# SCHE_TA_THI_THU_PHUONG.net
KiCad netlist of a schematic drawn in Altium Designer
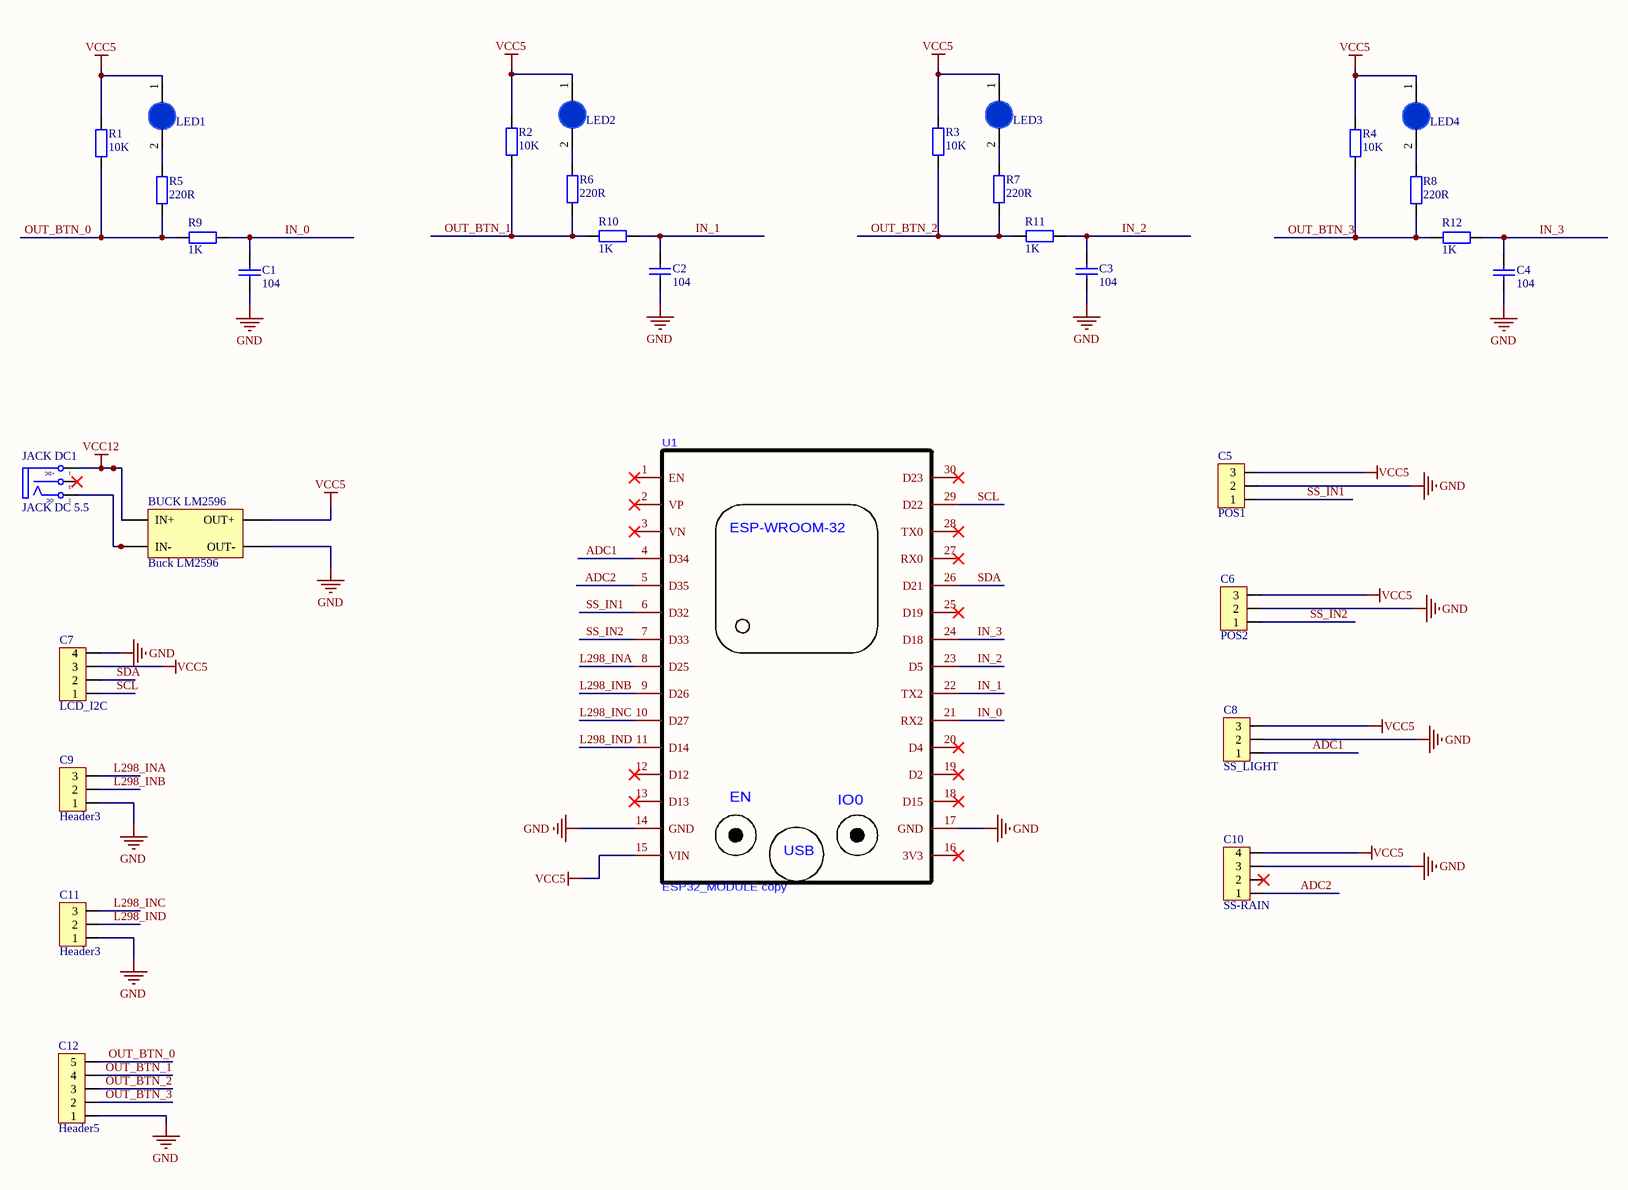
[diagram p0: SCHE_TA_THI_THU_PHUONG.SchDoc]

(export (version "E")
  (design (tool "Eeschema 10.0.6"))
  (components
    (comp (ref "BUCK LM2596")
      (value "Buck LM2596")
      (footprint "BUCK LM2596")
      (libsource (lib "myLib_v1 (1)") (part "Buck LM2596"))
    )
    (comp (ref "C1")
      (value "104")
      (footprint "tu gom")
      (description "Cắm")
      (libsource (lib "Altium_Lib_by_KhueNguyenCreator") (part "Tu gom 104 50V"))
    )
    (comp (ref "C2")
      (value "104")
      (footprint "tu gom")
      (description "Cắm")
      (libsource (lib "Altium_Lib_by_KhueNguyenCreator") (part "Tu gom 104 50V"))
    )
    (comp (ref "C3")
      (value "104")
      (footprint "tu gom")
      (description "Cắm")
      (libsource (lib "Altium_Lib_by_KhueNguyenCreator") (part "Tu gom 104 50V"))
    )
    (comp (ref "C4")
      (value "104")
      (footprint "tu gom")
      (description "Cắm")
      (libsource (lib "Altium_Lib_by_KhueNguyenCreator") (part "Tu gom 104 50V"))
    )
    (comp (ref "C5")
      (value "POS1")
      (footprint "Header3")
      (description "Header IDC, 3 x 1 Pin Vertical 2.54mm Pitch (Non-Boxed, Male)")
      (fields
        (field (name "MANUFACTURER") "Würth Elektronik eiSos GmbH")
        (field (name "PARTNO") "613002143121")
        (field (name "CREATED BY") "Karrer Zheng")
      )
      (libsource (lib "myLib_v1") (part "Header3"))
    )
    (comp (ref "C6")
      (value "POS2")
      (footprint "Header3")
      (description "Header IDC, 3 x 1 Pin Vertical 2.54mm Pitch (Non-Boxed, Male)")
      (fields
        (field (name "MANUFACTURER") "Würth Elektronik eiSos GmbH")
        (field (name "PARTNO") "613002143121")
        (field (name "CREATED BY") "Karrer Zheng")
      )
      (libsource (lib "myLib_v1") (part "Header3"))
    )
    (comp (ref "C7")
      (value "LCD_I2C")
      (footprint "Header4")
      (description "Header IDC, 4 x 1 Pin Vertical 2.54mm Pitch (Non-Boxed, Male)")
      (fields
        (field (name "MANUFACTURER") "Würth Elektronik eiSos GmbH")
        (field (name "PARTNO") "613002143121")
        (field (name "CREATED BY") "Karrer Zheng")
      )
      (libsource (lib "myLib_v1") (part "Header4"))
    )
    (comp (ref "C8")
      (value "SS_LIGHT")
      (footprint "Header3")
      (description "Header IDC, 3 x 1 Pin Vertical 2.54mm Pitch (Non-Boxed, Male)")
      (fields
        (field (name "MANUFACTURER") "Würth Elektronik eiSos GmbH")
        (field (name "PARTNO") "613002143121")
        (field (name "CREATED BY") "Karrer Zheng")
      )
      (libsource (lib "myLib_v1") (part "Header3"))
    )
    (comp (ref "C9")
      (value "Header3")
      (footprint "Header3")
      (description "Header IDC, 3 x 1 Pin Vertical 2.54mm Pitch (Non-Boxed, Male)")
      (fields
        (field (name "MANUFACTURER") "Würth Elektronik eiSos GmbH")
        (field (name "PARTNO") "613002143121")
        (field (name "CREATED BY") "Karrer Zheng")
      )
      (libsource (lib "myLib_v1") (part "Header3"))
    )
    (comp (ref "C10")
      (value "SS-RAIN")
      (footprint "Header4")
      (description "Header IDC, 4 x 1 Pin Vertical 2.54mm Pitch (Non-Boxed, Male)")
      (fields
        (field (name "MANUFACTURER") "Würth Elektronik eiSos GmbH")
        (field (name "PARTNO") "613002143121")
        (field (name "CREATED BY") "Karrer Zheng")
      )
      (libsource (lib "myLib_v1") (part "Header4"))
    )
    (comp (ref "C11")
      (value "Header3")
      (footprint "Header3")
      (description "Header IDC, 3 x 1 Pin Vertical 2.54mm Pitch (Non-Boxed, Male)")
      (fields
        (field (name "MANUFACTURER") "Würth Elektronik eiSos GmbH")
        (field (name "PARTNO") "613002143121")
        (field (name "CREATED BY") "Karrer Zheng")
      )
      (libsource (lib "myLib_v1") (part "Header3"))
    )
    (comp (ref "C12")
      (value "Header5")
      (footprint "Header5")
      (description "Header IDC, 5 x 1 Pin Vertical 2.54mm Pitch (Non-Boxed, Male)")
      (fields
        (field (name "MANUFACTURER") "Würth Elektronik eiSos GmbH")
        (field (name "PARTNO") "613002143121")
        (field (name "CREATED BY") "Karrer Zheng")
      )
      (libsource (lib "myLib_v1") (part "Header5"))
    )
    (comp (ref "JACK DC1")
      (value "JACK DC 5.5")
      (footprint "JACK DC 5.5")
      (libsource (lib "Altium_Lib_by_KhueNguyenCreator") (part "JACK DC 5.5"))
    )
    (comp (ref "LED1")
      (value "LED 3mm")
      (footprint "LED-3MM-BLUE")
      (description "Cắm")
      (libsource (lib "myLib_v1") (part "LED 3mm Xanh Duong"))
    )
    (comp (ref "LED2")
      (value "LED 3mm")
      (footprint "LED-3MM-BLUE")
      (description "Cắm")
      (libsource (lib "myLib_v1") (part "LED 3mm Xanh Duong"))
    )
    (comp (ref "LED3")
      (value "LED 3mm")
      (footprint "LED-3MM-BLUE")
      (description "Cắm")
      (libsource (lib "myLib_v1") (part "LED 3mm Xanh Duong"))
    )
    (comp (ref "LED4")
      (value "LED 3mm")
      (footprint "LED-3MM-BLUE")
      (description "Cắm")
      (libsource (lib "myLib_v1") (part "LED 3mm Xanh Duong"))
    )
    (comp (ref "R1")
      (value "10K")
      (footprint "R1/4W")
      (description "Resistor 1/4W")
      (libsource (lib "myLib_v1") (part "R1/4W"))
    )
    (comp (ref "R2")
      (value "10K")
      (footprint "R1/4W")
      (description "Resistor 1/4W")
      (libsource (lib "myLib_v1") (part "R1/4W"))
    )
    (comp (ref "R3")
      (value "10K")
      (footprint "R1/4W")
      (description "Resistor 1/4W")
      (libsource (lib "myLib_v1") (part "R1/4W"))
    )
    (comp (ref "R4")
      (value "10K")
      (footprint "R1/4W")
      (description "Resistor 1/4W")
      (libsource (lib "myLib_v1") (part "R1/4W"))
    )
    (comp (ref "R5")
      (value "220R")
      (footprint "R1/4W")
      (description "Resistor 1/4W")
      (libsource (lib "myLib_v1") (part "R1/4W"))
    )
    (comp (ref "R6")
      (value "220R")
      (footprint "R1/4W")
      (description "Resistor 1/4W")
      (libsource (lib "myLib_v1") (part "R1/4W"))
    )
    (comp (ref "R7")
      (value "220R")
      (footprint "R1/4W")
      (description "Resistor 1/4W")
      (libsource (lib "myLib_v1") (part "R1/4W"))
    )
    (comp (ref "R8")
      (value "220R")
      (footprint "R1/4W")
      (description "Resistor 1/4W")
      (libsource (lib "myLib_v1") (part "R1/4W"))
    )
    (comp (ref "R9")
      (value "1K")
      (footprint "R1/4W")
      (description "Resistor 1/4W")
      (libsource (lib "myLib_v1") (part "R1/4W"))
    )
    (comp (ref "R10")
      (value "1K")
      (footprint "R1/4W")
      (description "Resistor 1/4W")
      (libsource (lib "myLib_v1") (part "R1/4W"))
    )
    (comp (ref "R11")
      (value "1K")
      (footprint "R1/4W")
      (description "Resistor 1/4W")
      (libsource (lib "myLib_v1") (part "R1/4W"))
    )
    (comp (ref "R12")
      (value "1K")
      (footprint "R1/4W")
      (description "Resistor 1/4W")
      (libsource (lib "myLib_v1") (part "R1/4W"))
    )
    (comp (ref "U1")
      (value "ESP32_MODULE copy")
      (footprint "ESP32-WIFIMODULE-FOOTPRINT")
      (libsource (lib "myLib_v1") (part "ESP32_MODULE copy"))
    )
  )
  (nets
    (net (code "1") (name "/ADC1") (class "Default")
      (node (ref "C8") (pin "1") (pinfunction "1_1") (pintype "passive"))
      (node (ref "U1") (pin "4") (pinfunction "D34_4") (pintype "passive"))
    )
    (net (code "2") (name "/ADC2") (class "Default")
      (node (ref "C10") (pin "1") (pinfunction "1_1") (pintype "passive"))
      (node (ref "U1") (pin "5") (pinfunction "D35_5") (pintype "passive"))
    )
    (net (code "3") (name "/IN_0") (class "Default")
      (node (ref "C1") (pin "1") (pinfunction "1_1") (pintype "passive"))
      (node (ref "R9") (pin "1") (pinfunction "1_1") (pintype "passive"))
      (node (ref "U1") (pin "21") (pinfunction "RX2_21") (pintype "passive"))
    )
    (net (code "4") (name "/IN_1") (class "Default")
      (node (ref "C2") (pin "1") (pinfunction "1_1") (pintype "passive"))
      (node (ref "R10") (pin "1") (pinfunction "1_1") (pintype "passive"))
      (node (ref "U1") (pin "22") (pinfunction "TX2_22") (pintype "passive"))
    )
    (net (code "5") (name "/IN_2") (class "Default")
      (node (ref "C3") (pin "1") (pinfunction "1_1") (pintype "passive"))
      (node (ref "R11") (pin "1") (pinfunction "1_1") (pintype "passive"))
      (node (ref "U1") (pin "23") (pinfunction "D5_23") (pintype "passive"))
    )
    (net (code "6") (name "/IN_3") (class "Default")
      (node (ref "C4") (pin "1") (pinfunction "1_1") (pintype "passive"))
      (node (ref "R12") (pin "1") (pinfunction "1_1") (pintype "passive"))
      (node (ref "U1") (pin "24") (pinfunction "D18_24") (pintype "passive"))
    )
    (net (code "7") (name "/L298_INA") (class "Default")
      (node (ref "C9") (pin "3") (pinfunction "3_3") (pintype "passive"))
      (node (ref "U1") (pin "8") (pinfunction "D25_8") (pintype "passive"))
    )
    (net (code "8") (name "/L298_INB") (class "Default")
      (node (ref "C9") (pin "2") (pinfunction "2_2") (pintype "passive"))
      (node (ref "U1") (pin "9") (pinfunction "D26_9") (pintype "passive"))
    )
    (net (code "9") (name "/L298_INC") (class "Default")
      (node (ref "C11") (pin "3") (pinfunction "3_3") (pintype "passive"))
      (node (ref "U1") (pin "10") (pinfunction "D27_10") (pintype "passive"))
    )
    (net (code "10") (name "/L298_IND") (class "Default")
      (node (ref "C11") (pin "2") (pinfunction "2_2") (pintype "passive"))
      (node (ref "U1") (pin "11") (pinfunction "D14_11") (pintype "passive"))
    )
    (net (code "11") (name "/OUT_BTN_0") (class "Default")
      (node (ref "C12") (pin "5") (pinfunction "5_5") (pintype "passive"))
      (node (ref "R1") (pin "1") (pinfunction "1_1") (pintype "passive"))
      (node (ref "R5") (pin "1") (pinfunction "1_1") (pintype "passive"))
      (node (ref "R9") (pin "2") (pinfunction "2_2") (pintype "passive"))
    )
    (net (code "12") (name "/OUT_BTN_1") (class "Default")
      (node (ref "C12") (pin "4") (pinfunction "4_4") (pintype "passive"))
      (node (ref "R10") (pin "2") (pinfunction "2_2") (pintype "passive"))
      (node (ref "R2") (pin "1") (pinfunction "1_1") (pintype "passive"))
      (node (ref "R6") (pin "1") (pinfunction "1_1") (pintype "passive"))
    )
    (net (code "13") (name "/OUT_BTN_2") (class "Default")
      (node (ref "C12") (pin "3") (pinfunction "3_3") (pintype "passive"))
      (node (ref "R11") (pin "2") (pinfunction "2_2") (pintype "passive"))
      (node (ref "R3") (pin "1") (pinfunction "1_1") (pintype "passive"))
      (node (ref "R7") (pin "1") (pinfunction "1_1") (pintype "passive"))
    )
    (net (code "14") (name "/OUT_BTN_3") (class "Default")
      (node (ref "C12") (pin "2") (pinfunction "2_2") (pintype "passive"))
      (node (ref "R12") (pin "2") (pinfunction "2_2") (pintype "passive"))
      (node (ref "R4") (pin "1") (pinfunction "1_1") (pintype "passive"))
      (node (ref "R8") (pin "1") (pinfunction "1_1") (pintype "passive"))
    )
    (net (code "15") (name "/SCL") (class "Default")
      (node (ref "C7") (pin "1") (pinfunction "1_1") (pintype "passive"))
      (node (ref "U1") (pin "29") (pinfunction "D22_29") (pintype "passive"))
    )
    (net (code "16") (name "/SDA") (class "Default")
      (node (ref "C7") (pin "2") (pinfunction "2_2") (pintype "passive"))
      (node (ref "U1") (pin "26") (pinfunction "D21_26") (pintype "passive"))
    )
    (net (code "17") (name "/SS_IN1") (class "Default")
      (node (ref "C5") (pin "1") (pinfunction "1_1") (pintype "passive"))
      (node (ref "U1") (pin "6") (pinfunction "D32_6") (pintype "passive"))
    )
    (net (code "18") (name "/SS_IN2") (class "Default")
      (node (ref "C6") (pin "1") (pinfunction "1_1") (pintype "passive"))
      (node (ref "U1") (pin "7") (pinfunction "D33_7") (pintype "passive"))
    )
    (net (code "19") (name "GND") (class "Default")
      (node (ref "BUCK LM2596") (pin "3") (pinfunction "OUT-_3") (pintype "passive"))
      (node (ref "C1") (pin "2") (pinfunction "2_2") (pintype "passive"))
      (node (ref "C10") (pin "3") (pinfunction "3_3") (pintype "passive"))
      (node (ref "C11") (pin "1") (pinfunction "1_1") (pintype "passive"))
      (node (ref "C12") (pin "1") (pinfunction "1_1") (pintype "passive"))
      (node (ref "C2") (pin "2") (pinfunction "2_2") (pintype "passive"))
      (node (ref "C3") (pin "2") (pinfunction "2_2") (pintype "passive"))
      (node (ref "C4") (pin "2") (pinfunction "2_2") (pintype "passive"))
      (node (ref "C5") (pin "2") (pinfunction "2_2") (pintype "passive"))
      (node (ref "C6") (pin "2") (pinfunction "2_2") (pintype "passive"))
      (node (ref "C7") (pin "4") (pinfunction "4_4") (pintype "passive"))
      (node (ref "C8") (pin "2") (pinfunction "2_2") (pintype "passive"))
      (node (ref "C9") (pin "1") (pinfunction "1_1") (pintype "passive"))
      (node (ref "U1") (pin "14") (pinfunction "GND_14") (pintype "passive"))
      (node (ref "U1") (pin "17") (pinfunction "GND_17") (pintype "passive"))
    )
    (net (code "20") (name "Net-(BUCK LM2596-IN-)") (class "Default")
      (node (ref "BUCK LM2596") (pin "2") (pinfunction "IN-_2") (pintype "passive"))
      (node (ref "JACK DC1") (pin "2") (pinfunction "TN_2") (pintype "passive"))
    )
    (net (code "21") (name "Net-(LED1-K)") (class "Default")
      (node (ref "LED1") (pin "2") (pinfunction "K_2") (pintype "passive"))
      (node (ref "R5") (pin "2") (pinfunction "2_2") (pintype "passive"))
    )
    (net (code "22") (name "Net-(LED2-K)") (class "Default")
      (node (ref "LED2") (pin "2") (pinfunction "K_2") (pintype "passive"))
      (node (ref "R6") (pin "2") (pinfunction "2_2") (pintype "passive"))
    )
    (net (code "23") (name "Net-(LED3-K)") (class "Default")
      (node (ref "LED3") (pin "2") (pinfunction "K_2") (pintype "passive"))
      (node (ref "R7") (pin "2") (pinfunction "2_2") (pintype "passive"))
    )
    (net (code "24") (name "Net-(LED4-K)") (class "Default")
      (node (ref "LED4") (pin "2") (pinfunction "K_2") (pintype "passive"))
      (node (ref "R8") (pin "2") (pinfunction "2_2") (pintype "passive"))
    )
    (net (code "25") (name "VCC5") (class "Default")
      (node (ref "BUCK LM2596") (pin "4") (pinfunction "OUT+_4") (pintype "passive"))
      (node (ref "C10") (pin "4") (pinfunction "4_4") (pintype "passive"))
      (node (ref "C5") (pin "3") (pinfunction "3_3") (pintype "passive"))
      (node (ref "C6") (pin "3") (pinfunction "3_3") (pintype "passive"))
      (node (ref "C7") (pin "3") (pinfunction "3_3") (pintype "passive"))
      (node (ref "C8") (pin "3") (pinfunction "3_3") (pintype "passive"))
      (node (ref "LED1") (pin "1") (pinfunction "A_1") (pintype "passive"))
      (node (ref "LED2") (pin "1") (pinfunction "A_1") (pintype "passive"))
      (node (ref "LED3") (pin "1") (pinfunction "A_1") (pintype "passive"))
      (node (ref "LED4") (pin "1") (pinfunction "A_1") (pintype "passive"))
      (node (ref "R1") (pin "2") (pinfunction "2_2") (pintype "passive"))
      (node (ref "R2") (pin "2") (pinfunction "2_2") (pintype "passive"))
      (node (ref "R3") (pin "2") (pinfunction "2_2") (pintype "passive"))
      (node (ref "R4") (pin "2") (pinfunction "2_2") (pintype "passive"))
      (node (ref "U1") (pin "15") (pinfunction "VIN_15") (pintype "passive"))
    )
    (net (code "26") (name "VCC12") (class "Default")
      (node (ref "BUCK LM2596") (pin "1") (pinfunction "IN+_1") (pintype "passive"))
      (node (ref "JACK DC1") (pin "1") (pinfunction "T_1") (pintype "passive"))
    )
    (net (code "27") (name "unconnected-(C10-Pad2)") (class "Default")
      (node (ref "C10") (pin "2") (pinfunction "2_2") (pintype "passive+no_connect"))
    )
    (net (code "28") (name "unconnected-(JACK DC1-S-Pad3)") (class "Default")
      (node (ref "JACK DC1") (pin "3") (pinfunction "S_3") (pintype "power_in+no_connect"))
    )
    (net (code "29") (name "unconnected-(U1-3V3-Pad16)") (class "Default")
      (node (ref "U1") (pin "16") (pinfunction "3V3_16") (pintype "passive+no_connect"))
    )
    (net (code "30") (name "unconnected-(U1-D2-Pad19)") (class "Default")
      (node (ref "U1") (pin "19") (pinfunction "D2_19") (pintype "passive+no_connect"))
    )
    (net (code "31") (name "unconnected-(U1-D4-Pad20)") (class "Default")
      (node (ref "U1") (pin "20") (pinfunction "D4_20") (pintype "passive+no_connect"))
    )
    (net (code "32") (name "unconnected-(U1-D12-Pad12)") (class "Default")
      (node (ref "U1") (pin "12") (pinfunction "D12_12") (pintype "passive+no_connect"))
    )
    (net (code "33") (name "unconnected-(U1-D13-Pad13)") (class "Default")
      (node (ref "U1") (pin "13") (pinfunction "D13_13") (pintype "passive+no_connect"))
    )
    (net (code "34") (name "unconnected-(U1-D15-Pad18)") (class "Default")
      (node (ref "U1") (pin "18") (pinfunction "D15_18") (pintype "passive+no_connect"))
    )
    (net (code "35") (name "unconnected-(U1-D19-Pad25)") (class "Default")
      (node (ref "U1") (pin "25") (pinfunction "D19_25") (pintype "passive+no_connect"))
    )
    (net (code "36") (name "unconnected-(U1-D23-Pad30)") (class "Default")
      (node (ref "U1") (pin "30") (pinfunction "D23_30") (pintype "passive+no_connect"))
    )
    (net (code "37") (name "unconnected-(U1-EN-Pad1)") (class "Default")
      (node (ref "U1") (pin "1") (pinfunction "EN_1") (pintype "passive+no_connect"))
    )
    (net (code "38") (name "unconnected-(U1-RX0-Pad27)") (class "Default")
      (node (ref "U1") (pin "27") (pinfunction "RX0_27") (pintype "passive+no_connect"))
    )
    (net (code "39") (name "unconnected-(U1-TX0-Pad28)") (class "Default")
      (node (ref "U1") (pin "28") (pinfunction "TX0_28") (pintype "passive+no_connect"))
    )
    (net (code "40") (name "unconnected-(U1-VN-Pad3)") (class "Default")
      (node (ref "U1") (pin "3") (pinfunction "VN_3") (pintype "passive+no_connect"))
    )
    (net (code "41") (name "unconnected-(U1-VP-Pad2)") (class "Default")
      (node (ref "U1") (pin "2") (pinfunction "VP_2") (pintype "passive+no_connect"))
    )
  )
)
